# radio_module.net
KiCad netlist of a schematic drawn in EAGLE
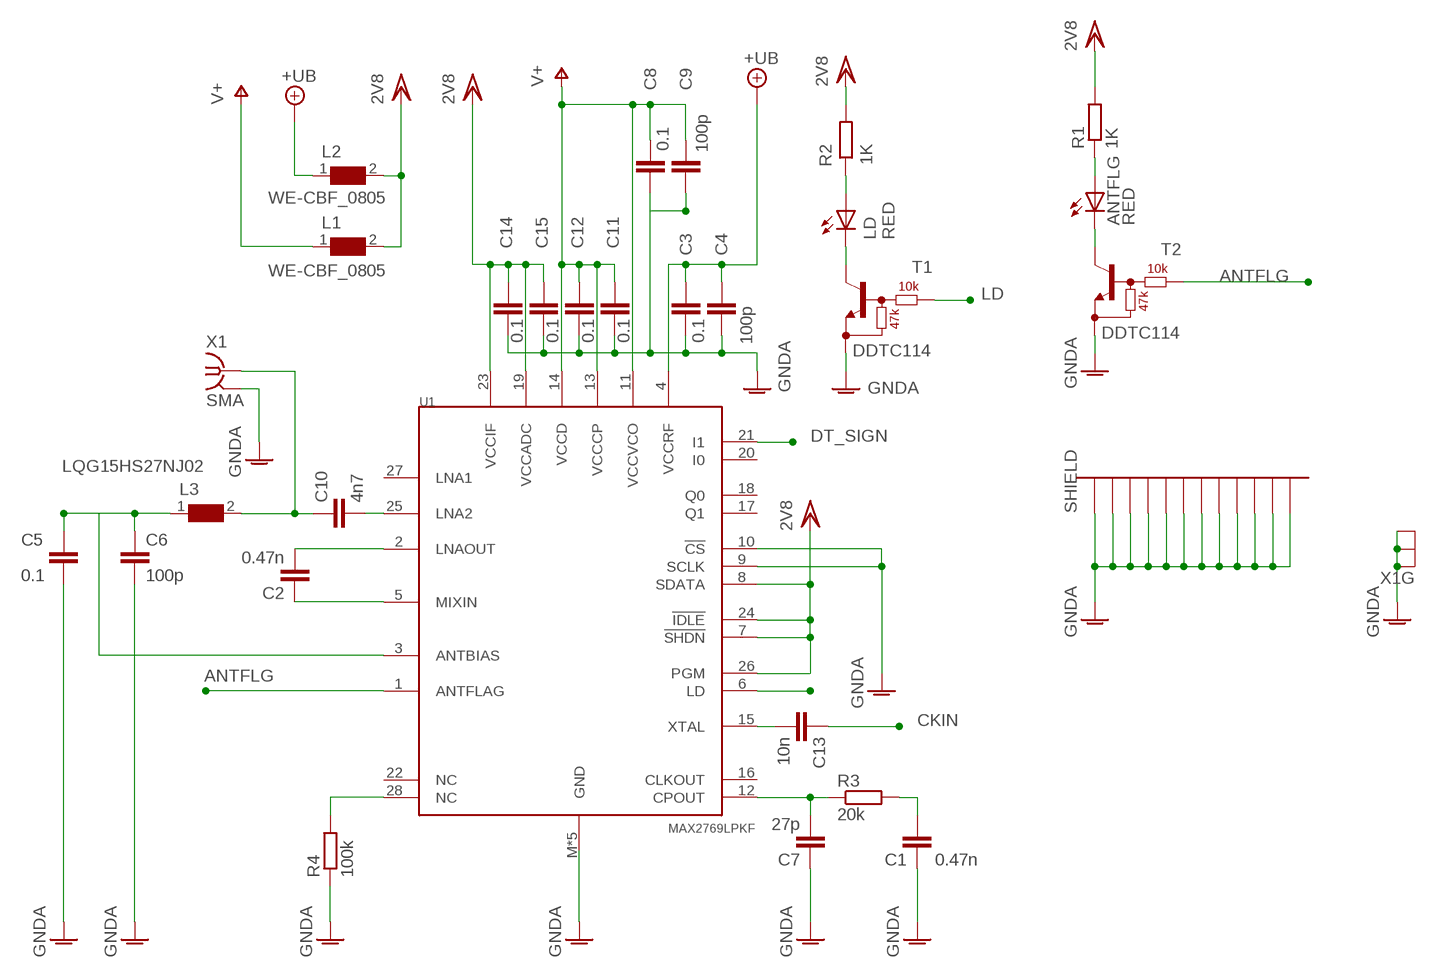
[diagram p0: schematic, sheet 1]

(export (version "E")
  (design (tool "Eeschema 10.0.6"))
  (components
    (comp (ref "ANTFLG")
      (value "RED")
      (footprint "eagle-import:CHIP-LED0603")
      (libsource (lib "eagle-import") (part "LEDCHIP-LED0603"))
    )
    (comp (ref "C1")
      (value "0.47n")
      (footprint "eagle-import:C0402")
      (libsource (lib "eagle-import") (part "rcl_1_C-EUC0402"))
    )
    (comp (ref "C2")
      (value "0.47n")
      (footprint "eagle-import:C0402")
      (libsource (lib "eagle-import") (part "rcl_1_C-EUC0402"))
    )
    (comp (ref "C3")
      (value "0.1")
      (footprint "eagle-import:C0402")
      (libsource (lib "eagle-import") (part "rcl_1_C-EUC0402"))
    )
    (comp (ref "C4")
      (value "100p")
      (footprint "eagle-import:C0402")
      (libsource (lib "eagle-import") (part "rcl_1_C-EUC0402"))
    )
    (comp (ref "C5")
      (value "0.1")
      (footprint "eagle-import:C0603")
      (libsource (lib "eagle-import") (part "C-EUC0603"))
    )
    (comp (ref "C6")
      (value "100p")
      (footprint "eagle-import:C0402")
      (libsource (lib "eagle-import") (part "rcl_1_C-EUC0402"))
    )
    (comp (ref "C7")
      (value "27p")
      (footprint "eagle-import:C0402")
      (libsource (lib "eagle-import") (part "rcl_1_C-EUC0402"))
    )
    (comp (ref "C8")
      (value "0.1")
      (footprint "eagle-import:C0402")
      (libsource (lib "eagle-import") (part "rcl_1_C-EUC0402"))
    )
    (comp (ref "C9")
      (value "100p")
      (footprint "eagle-import:C0402")
      (libsource (lib "eagle-import") (part "rcl_1_C-EUC0402"))
    )
    (comp (ref "C10")
      (value "4n7")
      (footprint "eagle-import:C0402")
      (libsource (lib "eagle-import") (part "rcl_1_C-EUC0402"))
    )
    (comp (ref "C11")
      (value "0.1")
      (footprint "eagle-import:C0402")
      (libsource (lib "eagle-import") (part "rcl_1_C-EUC0402"))
    )
    (comp (ref "C12")
      (value "0.1")
      (footprint "eagle-import:C0402")
      (libsource (lib "eagle-import") (part "rcl_1_C-EUC0402"))
    )
    (comp (ref "C13")
      (value "10n")
      (footprint "eagle-import:C0402")
      (libsource (lib "eagle-import") (part "rcl_1_C-EUC0402"))
    )
    (comp (ref "C14")
      (value "0.1")
      (footprint "eagle-import:C0402")
      (libsource (lib "eagle-import") (part "rcl_1_C-EUC0402"))
    )
    (comp (ref "C15")
      (value "0.1")
      (footprint "eagle-import:C0402")
      (libsource (lib "eagle-import") (part "rcl_1_C-EUC0402"))
    )
    (comp (ref "L1")
      (value "WE-CBF_0805")
      (footprint "eagle-import:0805")
      (libsource (lib "eagle-import") (part "WE-CBF_0805"))
    )
    (comp (ref "L2")
      (value "WE-CBF_0805")
      (footprint "eagle-import:0805")
      (libsource (lib "eagle-import") (part "WE-CBF_0805"))
    )
    (comp (ref "L3")
      (value "LQG15HS27NJ02")
      (footprint "eagle-import:0402")
      (libsource (lib "eagle-import") (part "WE-MK_0402"))
    )
    (comp (ref "LD")
      (value "RED")
      (footprint "eagle-import:CHIP-LED0603")
      (libsource (lib "eagle-import") (part "LEDCHIP-LED0603"))
    )
    (comp (ref "R1")
      (value "1K")
      (footprint "eagle-import:R0402")
      (libsource (lib "eagle-import") (part "R-EU_R0402"))
    )
    (comp (ref "R2")
      (value "1K")
      (footprint "eagle-import:R0402")
      (libsource (lib "eagle-import") (part "R-EU_R0402"))
    )
    (comp (ref "R3")
      (value "20k")
      (footprint "eagle-import:R0402")
      (libsource (lib "eagle-import") (part "R-EU_R0402"))
    )
    (comp (ref "R4")
      (value "100k")
      (footprint "eagle-import:R0402")
      (libsource (lib "eagle-import") (part "R-EU_R0402"))
    )
    (comp (ref "S2")
      (value "BMIS-202")
      (footprint "eagle-import:BMIS-202")
      (libsource (lib "eagle-import") (part "BMIS-202"))
    )
    (comp (ref "T1")
      (value "DDTC114")
      (footprint "eagle-import:SOT323-R_INFINEON")
      (libsource (lib "eagle-import") (part "BCR135W"))
    )
    (comp (ref "T2")
      (value "DDTC114")
      (footprint "eagle-import:SOT323-R_INFINEON")
      (libsource (lib "eagle-import") (part "BCR135W"))
    )
    (comp (ref "U1")
      (value "MAX2769LPKF")
      (footprint "eagle-import:QFN28LPKF")
      (libsource (lib "eagle-import") (part "MAX2769LPKF"))
    )
    (comp (ref "X1")
      (value "SMA")
      (footprint "eagle-import:J502-ND-142-0701-801_806")
      (fields (field (name "MF") "JOHNSON COMPONENTS") (field (name "MPN") "142-0701-801"))
      (libsource (lib "eagle-import") (part "SMA-142-0701-801/806"))
    )
  )
  (nets
    (net (code "1") (name "+UB") (class "Default")
      (node (ref "C3") (pin "1") (pinfunction "1_1") (pintype "passive"))
      (node (ref "C4") (pin "1") (pinfunction "1_1") (pintype "passive"))
      (node (ref "L2") (pin "1") (pinfunction "1_1") (pintype "passive"))
      (node (ref "U1") (pin "4") (pinfunction "VCCRF_4") (pintype "power_in"))
    )
    (net (code "2") (name "/ANTFLG") (class "Default")
      (node (ref "T2") (pin "1") (pinfunction "B_1") (pintype "passive"))
      (node (ref "U1") (pin "1") (pinfunction "ANTFLAG_1") (pintype "output"))
    )
    (net (code "3") (name "/CKIN") (class "Default")
      (node (ref "C13") (pin "1") (pinfunction "1_1") (pintype "passive"))
    )
    (net (code "4") (name "/DT_SIGN") (class "Default")
      (node (ref "U1") (pin "21") (pinfunction "I1_21") (pintype "output"))
    )
    (net (code "5") (name "/LD") (class "Default")
      (node (ref "T1") (pin "1") (pinfunction "B_1") (pintype "passive"))
      (node (ref "U1") (pin "6") (pinfunction "LD_6") (pintype "output"))
    )
    (net (code "6") (name "2V8") (class "Default")
      (node (ref "C14") (pin "1") (pinfunction "1_1") (pintype "passive"))
      (node (ref "C15") (pin "1") (pinfunction "1_1") (pintype "passive"))
      (node (ref "L1") (pin "2") (pinfunction "2_2") (pintype "passive"))
      (node (ref "L2") (pin "2") (pinfunction "2_2") (pintype "passive"))
      (node (ref "R1") (pin "2") (pinfunction "2_2") (pintype "passive"))
      (node (ref "R2") (pin "2") (pinfunction "2_2") (pintype "passive"))
      (node (ref "U1") (pin "19") (pinfunction "VCCADC_19") (pintype "power_in"))
      (node (ref "U1") (pin "23") (pinfunction "VCCIF_23") (pintype "power_in"))
      (node (ref "U1") (pin "24") (pinfunction "~{IDLE}_24") (pintype "input"))
      (node (ref "U1") (pin "26") (pinfunction "PGM_26") (pintype "input"))
      (node (ref "U1") (pin "7") (pinfunction "~{SHDN}_7") (pintype "input"))
      (node (ref "U1") (pin "8") (pinfunction "SDATA_8") (pintype "input"))
    )
    (net (code "7") (name "GNDA") (class "Default")
      (node (ref "C1") (pin "1") (pinfunction "1_1") (pintype "passive"))
      (node (ref "C11") (pin "2") (pinfunction "2_2") (pintype "passive"))
      (node (ref "C12") (pin "2") (pinfunction "2_2") (pintype "passive"))
      (node (ref "C14") (pin "2") (pinfunction "2_2") (pintype "passive"))
      (node (ref "C15") (pin "2") (pinfunction "2_2") (pintype "passive"))
      (node (ref "C3") (pin "2") (pinfunction "2_2") (pintype "passive"))
      (node (ref "C4") (pin "2") (pinfunction "2_2") (pintype "passive"))
      (node (ref "C5") (pin "2") (pinfunction "2_2") (pintype "passive"))
      (node (ref "C6") (pin "2") (pinfunction "2_2") (pintype "passive"))
      (node (ref "C7") (pin "1") (pinfunction "1_1") (pintype "passive"))
      (node (ref "C8") (pin "2") (pinfunction "2_2") (pintype "passive"))
      (node (ref "C9") (pin "2") (pinfunction "2_2") (pintype "passive"))
      (node (ref "R4") (pin "1") (pinfunction "1_1") (pintype "passive"))
      (node (ref "S2") (pin "P$1") (pinfunction "GND_P$1") (pintype "power_in"))
      (node (ref "S2") (pin "P$10") (pinfunction "GND_P$10") (pintype "power_in"))
      (node (ref "S2") (pin "P$11") (pinfunction "GND_P$11") (pintype "power_in"))
      (node (ref "S2") (pin "P$12") (pinfunction "GND_P$12") (pintype "power_in"))
      (node (ref "S2") (pin "P$2") (pinfunction "GND_P$2") (pintype "power_in"))
      (node (ref "S2") (pin "P$3") (pinfunction "GND_P$3") (pintype "power_in"))
      (node (ref "S2") (pin "P$4") (pinfunction "GND_P$4") (pintype "power_in"))
      (node (ref "S2") (pin "P$5") (pinfunction "GND_P$5") (pintype "power_in"))
      (node (ref "S2") (pin "P$6") (pinfunction "GND_P$6") (pintype "power_in"))
      (node (ref "S2") (pin "P$7") (pinfunction "GND_P$7") (pintype "power_in"))
      (node (ref "S2") (pin "P$8") (pinfunction "GND_P$8") (pintype "power_in"))
      (node (ref "S2") (pin "P$9") (pinfunction "GND_P$9") (pintype "power_in"))
      (node (ref "T1") (pin "2") (pinfunction "E_2") (pintype "passive"))
      (node (ref "T2") (pin "2") (pinfunction "E_2") (pintype "passive"))
      (node (ref "U1") (pin "10") (pinfunction "~{CS}_10") (pintype "input"))
      (node (ref "U1") (pin "9") (pinfunction "SCLK_9") (pintype "input"))
      (node (ref "U1") (pin "M") (pinfunction "GND_M") (pintype "power_in"))
      (node (ref "U1") (pin "P$4") (pinfunction "GND_P$4") (pintype "power_in"))
      (node (ref "U1") (pin "P$6") (pinfunction "GND_P$6") (pintype "power_in"))
      (node (ref "U1") (pin "P$7") (pinfunction "GND_P$7") (pintype "power_in"))
      (node (ref "U1") (pin "P$9") (pinfunction "GND_P$9") (pintype "power_in"))
      (node (ref "X1") (pin "G@1") (pinfunction "GND_G@1") (pintype "power_in"))
      (node (ref "X1") (pin "G@2") (pinfunction "GND_G@2") (pintype "power_in"))
      (node (ref "X1") (pin "G@3") (pinfunction "GND_G@3") (pintype "power_in"))
      (node (ref "X1") (pin "G@4") (pinfunction "GND_G@4") (pintype "power_in"))
    )
    (net (code "8") (name "Net-(ANTFLG-PadA)") (class "Default")
      (node (ref "ANTFLG") (pin "A") (pinfunction "A_A") (pintype "passive"))
      (node (ref "R1") (pin "1") (pinfunction "1_1") (pintype "passive"))
    )
    (net (code "9") (name "Net-(C1-Pad2)") (class "Default")
      (node (ref "C1") (pin "2") (pinfunction "2_2") (pintype "passive"))
      (node (ref "R3") (pin "2") (pinfunction "2_2") (pintype "passive"))
    )
    (net (code "10") (name "Net-(C10-Pad1)") (class "Default")
      (node (ref "C10") (pin "1") (pinfunction "1_1") (pintype "passive"))
      (node (ref "L3") (pin "2") (pinfunction "2_2") (pintype "passive"))
      (node (ref "X1") (pin "1") (pinfunction "1_1") (pintype "passive"))
    )
    (net (code "11") (name "Net-(LD-PadA)") (class "Default")
      (node (ref "LD") (pin "A") (pinfunction "A_A") (pintype "passive"))
      (node (ref "R2") (pin "1") (pinfunction "1_1") (pintype "passive"))
    )
    (net (code "12") (name "Net-(T1-C)") (class "Default")
      (node (ref "LD") (pin "C") (pinfunction "C_C") (pintype "passive"))
      (node (ref "T1") (pin "3") (pinfunction "C_3") (pintype "passive"))
    )
    (net (code "13") (name "Net-(T2-C)") (class "Default")
      (node (ref "ANTFLG") (pin "C") (pinfunction "C_C") (pintype "passive"))
      (node (ref "T2") (pin "3") (pinfunction "C_3") (pintype "passive"))
    )
    (net (code "14") (name "Net-(U1-ANTBIAS)") (class "Default")
      (node (ref "C5") (pin "1") (pinfunction "1_1") (pintype "passive"))
      (node (ref "C6") (pin "1") (pinfunction "1_1") (pintype "passive"))
      (node (ref "L3") (pin "1") (pinfunction "1_1") (pintype "passive"))
      (node (ref "U1") (pin "3") (pinfunction "ANTBIAS_3") (pintype "output"))
    )
    (net (code "15") (name "Net-(U1-CPOUT)") (class "Default")
      (node (ref "C7") (pin "2") (pinfunction "2_2") (pintype "passive"))
      (node (ref "R3") (pin "1") (pinfunction "1_1") (pintype "passive"))
      (node (ref "U1") (pin "12") (pinfunction "CPOUT_12") (pintype "output"))
    )
    (net (code "16") (name "Net-(U1-LNA2)") (class "Default")
      (node (ref "C10") (pin "2") (pinfunction "2_2") (pintype "passive"))
      (node (ref "U1") (pin "25") (pinfunction "LNA2_25") (pintype "input"))
    )
    (net (code "17") (name "Net-(U1-LNAOUT)") (class "Default")
      (node (ref "C2") (pin "2") (pinfunction "2_2") (pintype "passive"))
      (node (ref "U1") (pin "2") (pinfunction "LNAOUT_2") (pintype "output"))
    )
    (net (code "18") (name "Net-(U1-MIXIN)") (class "Default")
      (node (ref "C2") (pin "1") (pinfunction "1_1") (pintype "passive"))
      (node (ref "U1") (pin "5") (pinfunction "MIXIN_5") (pintype "input"))
    )
    (net (code "19") (name "Net-(U1-NC)") (class "Default")
      (node (ref "R4") (pin "2") (pinfunction "2_2") (pintype "passive"))
      (node (ref "U1") (pin "28") (pinfunction "NC_28") (pintype "output"))
    )
    (net (code "20") (name "Net-(U1-XTAL)") (class "Default")
      (node (ref "C13") (pin "2") (pinfunction "2_2") (pintype "passive"))
      (node (ref "U1") (pin "15") (pinfunction "XTAL_15") (pintype "input"))
    )
    (net (code "21") (name "V+") (class "Default")
      (node (ref "C11") (pin "1") (pinfunction "1_1") (pintype "passive"))
      (node (ref "C12") (pin "1") (pinfunction "1_1") (pintype "passive"))
      (node (ref "C8") (pin "1") (pinfunction "1_1") (pintype "passive"))
      (node (ref "C9") (pin "1") (pinfunction "1_1") (pintype "passive"))
      (node (ref "L1") (pin "1") (pinfunction "1_1") (pintype "passive"))
      (node (ref "U1") (pin "11") (pinfunction "VCCVCO_11") (pintype "power_in"))
      (node (ref "U1") (pin "13") (pinfunction "VCCCP_13") (pintype "power_in"))
      (node (ref "U1") (pin "14") (pinfunction "VCCD_14") (pintype "power_in"))
    )
    (net (code "22") (name "unconnected-(U1-CLKOUT-Pad16)") (class "Default")
      (node (ref "U1") (pin "16") (pinfunction "CLKOUT_16") (pintype "output"))
    )
    (net (code "23") (name "unconnected-(U1-I0-Pad20)") (class "Default")
      (node (ref "U1") (pin "20") (pinfunction "I0_20") (pintype "output"))
    )
    (net (code "24") (name "unconnected-(U1-LNA1-Pad27)") (class "Default")
      (node (ref "U1") (pin "27") (pinfunction "LNA1_27") (pintype "input"))
    )
    (net (code "25") (name "unconnected-(U1-NC-Pad22)") (class "Default")
      (node (ref "U1") (pin "22") (pinfunction "NC_22") (pintype "no_connect"))
    )
    (net (code "26") (name "unconnected-(U1-Q0-Pad18)") (class "Default")
      (node (ref "U1") (pin "18") (pinfunction "Q0_18") (pintype "output"))
    )
    (net (code "27") (name "unconnected-(U1-Q1-Pad17)") (class "Default")
      (node (ref "U1") (pin "17") (pinfunction "Q1_17") (pintype "output"))
    )
  )
)
